# theMonarchTransmitter.net
KiCad netlist of a schematic drawn in Altium Designer
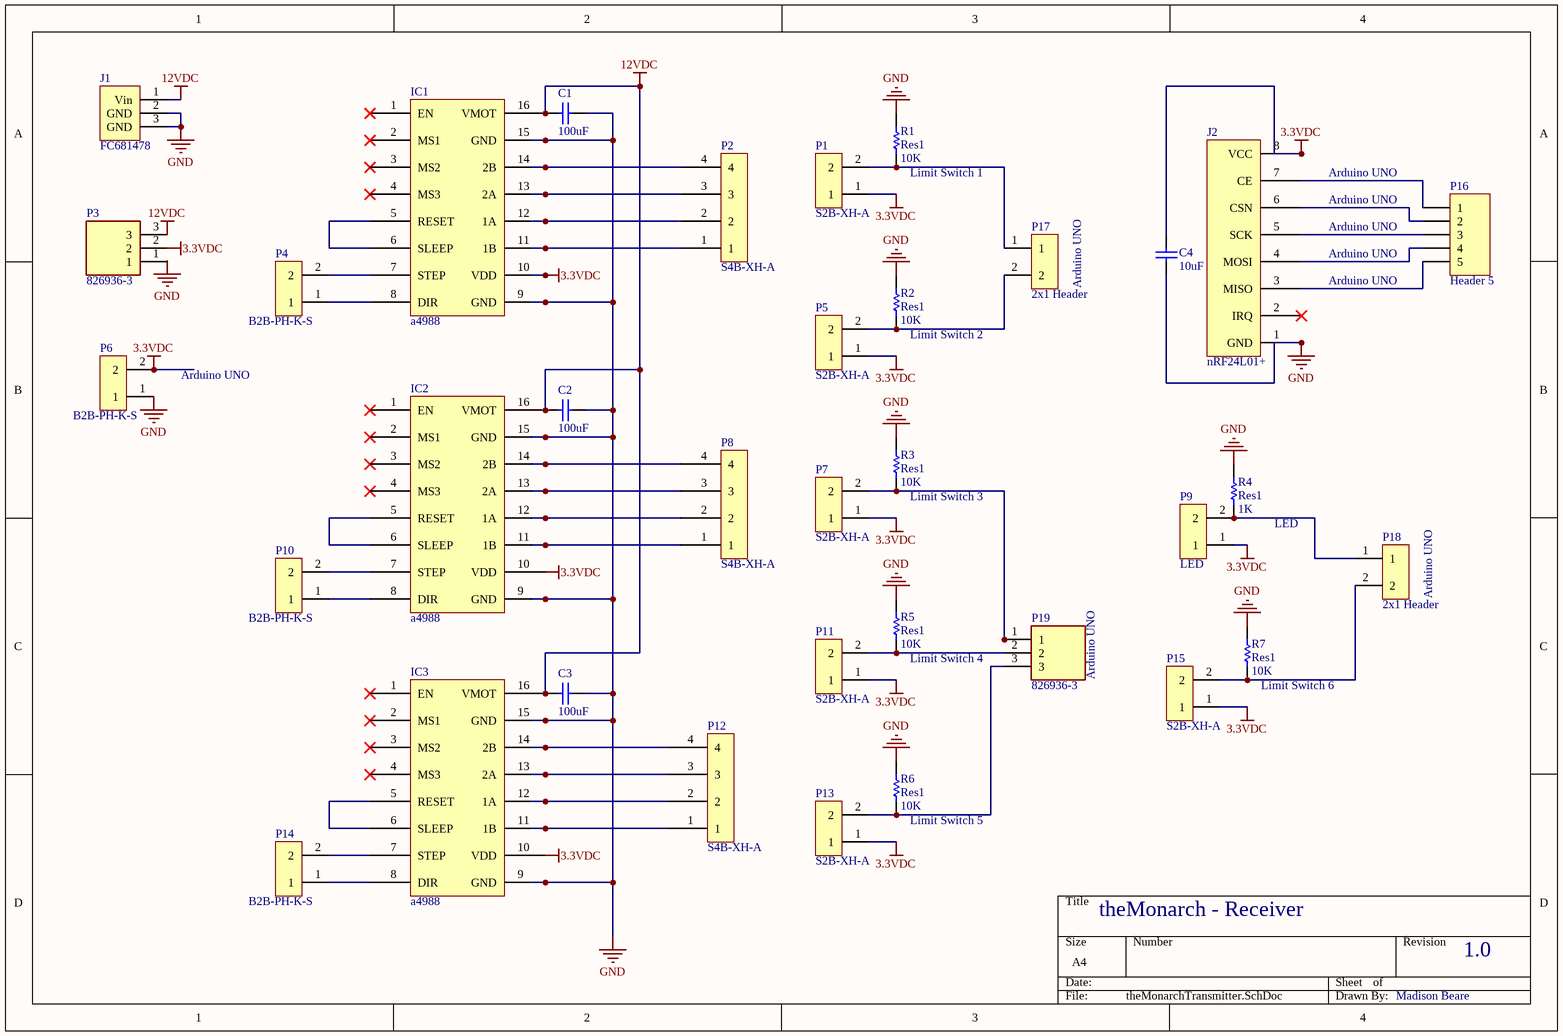
[diagram p0: theMonarchTransmitter.SchDoc]

(export (version "E")
  (design (tool "Eeschema 10.0.6"))
  (components
    (comp (ref "C1")
      (value "100uF")
      (footprint "RAD-0.3")
      (description "Capacitor")
      (fields (field (name "PUBLISHER") "Altium Limited"))
      (libsource (lib "Miscellaneous Devices") (part "Cap"))
    )
    (comp (ref "C2")
      (value "100uF")
      (footprint "RAD-0.3")
      (description "Capacitor")
      (fields (field (name "PUBLISHER") "Altium Limited"))
      (libsource (lib "Miscellaneous Devices") (part "Cap"))
    )
    (comp (ref "C3")
      (value "100uF")
      (footprint "RAD-0.3")
      (description "Capacitor")
      (fields (field (name "PUBLISHER") "Altium Limited"))
      (libsource (lib "Miscellaneous Devices") (part "Cap"))
    )
    (comp (ref "C4")
      (value "10uF")
      (footprint "RAD-0.3")
      (description "Capacitor")
      (fields (field (name "PUBLISHER") "Altium Limited"))
      (libsource (lib "Miscellaneous Devices") (part "Cap"))
    )
    (comp (ref "IC1")
      (value "a4988")
      (footprint "MODULE_A4988_STEPPER_MOTOR_DRIVER_CARRIER")
      (libsource (lib "theMonarchTransmitter_SchLib") (part "a4988"))
    )
    (comp (ref "IC2")
      (value "a4988")
      (footprint "MODULE_A4988_STEPPER_MOTOR_DRIVER_CARRIER")
      (libsource (lib "theMonarchTransmitter_SchLib") (part "a4988"))
    )
    (comp (ref "IC3")
      (value "a4988")
      (footprint "MODULE_A4988_STEPPER_MOTOR_DRIVER_CARRIER")
      (libsource (lib "theMonarchTransmitter_SchLib") (part "a4988"))
    )
    (comp (ref "J1")
      (value "FC681478")
      (footprint "FC681478")
      (description "CLIFF ELECTRONIC COMPONENTS         FC681478            CONNECTOR, POWER ENTRY, RCPT, 2A, 16VDC")
      (fields (field (name "MANUFACTURER") "Cliff"))
      (libsource (lib "theMonarchTransmitter_SchLib") (part "FC681478"))
    )
    (comp (ref "J2")
      (value "nRF24L01+")
      (footprint "TE_5-146278-8")
      (description "SPARKFUN TRANSCEIVER BREAKOUT -")
      (fields (field (name "MANUFACTURER") "SparkFun") (field (name "MANUFACTURER PART NUMBER") "WRL-00691"))
      (libsource (lib "theMonarchTransmitter_SchLib") (part "WRL-00691"))
    )
    (comp (ref "P1")
      (value "S2B-XH-A")
      (footprint "JST_S2B-XH-A(LF)(SN)")
      (description "Conn Shrouded Header HDR 2 POS 2.5mm Solder RA Thru-Hole Box")
      (fields
        (field (name "MANUFACTURER") "JST")
        (field (name "MANUFACTURER PART NUMBER") "S2B-XH-A(LF)(SN)")
      )
      (libsource (lib "theMonarchTransmitter_SchLib") (part "S2B-XH-A(LF)(SN)"))
    )
    (comp (ref "P2")
      (value "S4B-XH-A")
      (footprint "S4B-XH-A(LF)(SN)")
      (description "Conn Shrouded Header HDR 4 POS 2.5mm Solder RA Thru-Hole Box")
      (fields
        (field (name "MANUFACTURER") "JST")
        (field (name "MANUFACTURER PART NUMBER") "S4B-XH-A(LF)(SN)")
      )
      (libsource (lib "theMonarchTransmitter_SchLib") (part "S4B-XH-A(LF)(SN)"))
    )
    (comp (ref "P3")
      (value "826936-3")
      (footprint "TE_826936-3")
      (description "Connector Header Through Hole 3 position 0.100 (2.54mm)")
      (fields (field (name "MF") "TE Connectivity"))
      (libsource (lib "826936-3") (part "826936-3"))
    )
    (comp (ref "P4")
      (value "B2B-PH-K-S")
      (footprint "JST_B2B-PH-K-S(LF)(SN)")
      (description "Connector Header, PH Series, 2 Position, 2.00mm, Through Hole, Press-Fit, Solder, Natural")
      (fields
        (field (name "MANUFACTURER") "JST")
        (field (name "MANUFACTURER PART NUMBER") "B2B-PH-K-S(LF)(SN)")
      )
      (libsource (lib "theMonarchTransmitter_SchLib") (part "B2B-PH-K-S(LF)(SN)"))
    )
    (comp (ref "P5")
      (value "S2B-XH-A")
      (footprint "JST_S2B-XH-A(LF)(SN)")
      (description "Conn Shrouded Header HDR 2 POS 2.5mm Solder RA Thru-Hole Box")
      (fields
        (field (name "MANUFACTURER") "JST")
        (field (name "MANUFACTURER PART NUMBER") "S2B-XH-A(LF)(SN)")
      )
      (libsource (lib "theMonarchTransmitter_SchLib") (part "S2B-XH-A(LF)(SN)"))
    )
    (comp (ref "P6")
      (value "B2B-PH-K-S")
      (footprint "JST_B2B-PH-K-S(LF)(SN)")
      (description "Connector Header, PH Series, 2 Position, 2.00mm, Through Hole, Press-Fit, Solder, Natural")
      (fields
        (field (name "MANUFACTURER") "JST")
        (field (name "MANUFACTURER PART NUMBER") "B2B-PH-K-S(LF)(SN)")
      )
      (libsource (lib "theMonarchTransmitter_SchLib") (part "B2B-PH-K-S(LF)(SN)"))
    )
    (comp (ref "P7")
      (value "S2B-XH-A")
      (footprint "JST_S2B-XH-A(LF)(SN)")
      (description "Conn Shrouded Header HDR 2 POS 2.5mm Solder RA Thru-Hole Box")
      (fields
        (field (name "MANUFACTURER") "JST")
        (field (name "MANUFACTURER PART NUMBER") "S2B-XH-A(LF)(SN)")
      )
      (libsource (lib "theMonarchTransmitter_SchLib") (part "S2B-XH-A(LF)(SN)"))
    )
    (comp (ref "P8")
      (value "S4B-XH-A")
      (footprint "S4B-XH-A(LF)(SN)")
      (description "Conn Shrouded Header HDR 4 POS 2.5mm Solder RA Thru-Hole Box")
      (fields
        (field (name "MANUFACTURER") "JST")
        (field (name "MANUFACTURER PART NUMBER") "S4B-XH-A(LF)(SN)")
      )
      (libsource (lib "theMonarchTransmitter_SchLib") (part "S4B-XH-A(LF)(SN)"))
    )
    (comp (ref "P9")
      (value "LED")
      (footprint "HDR1X2")
      (description "Conn Shrouded Header HDR 2 POS 2.5mm Solder RA Thru-Hole Box")
      (fields
        (field (name "MANUFACTURER") "JST")
        (field (name "MANUFACTURER PART NUMBER") "S2B-XH-A(LF)(SN)")
      )
      (libsource (lib "theMonarchTransmitter_SchLib") (part "S2B-XH-A(LF)(SN)"))
    )
    (comp (ref "P10")
      (value "B2B-PH-K-S")
      (footprint "JST_B2B-PH-K-S(LF)(SN)")
      (description "Connector Header, PH Series, 2 Position, 2.00mm, Through Hole, Press-Fit, Solder, Natural")
      (fields
        (field (name "MANUFACTURER") "JST")
        (field (name "MANUFACTURER PART NUMBER") "B2B-PH-K-S(LF)(SN)")
      )
      (libsource (lib "theMonarchTransmitter_SchLib") (part "B2B-PH-K-S(LF)(SN)"))
    )
    (comp (ref "P11")
      (value "S2B-XH-A")
      (footprint "JST_S2B-XH-A(LF)(SN)")
      (description "Conn Shrouded Header HDR 2 POS 2.5mm Solder RA Thru-Hole Box")
      (fields
        (field (name "MANUFACTURER") "JST")
        (field (name "MANUFACTURER PART NUMBER") "S2B-XH-A(LF)(SN)")
      )
      (libsource (lib "theMonarchTransmitter_SchLib") (part "S2B-XH-A(LF)(SN)"))
    )
    (comp (ref "P12")
      (value "S4B-XH-A")
      (footprint "S4B-XH-A(LF)(SN)")
      (description "Conn Shrouded Header HDR 4 POS 2.5mm Solder RA Thru-Hole Box")
      (fields
        (field (name "MANUFACTURER") "JST")
        (field (name "MANUFACTURER PART NUMBER") "S4B-XH-A(LF)(SN)")
      )
      (libsource (lib "theMonarchTransmitter_SchLib") (part "S4B-XH-A(LF)(SN)"))
    )
    (comp (ref "P13")
      (value "S2B-XH-A")
      (footprint "JST_S2B-XH-A(LF)(SN)")
      (description "Conn Shrouded Header HDR 2 POS 2.5mm Solder RA Thru-Hole Box")
      (fields
        (field (name "MANUFACTURER") "JST")
        (field (name "MANUFACTURER PART NUMBER") "S2B-XH-A(LF)(SN)")
      )
      (libsource (lib "theMonarchTransmitter_SchLib") (part "S2B-XH-A(LF)(SN)"))
    )
    (comp (ref "P14")
      (value "B2B-PH-K-S")
      (footprint "JST_B2B-PH-K-S(LF)(SN)")
      (description "Connector Header, PH Series, 2 Position, 2.00mm, Through Hole, Press-Fit, Solder, Natural")
      (fields
        (field (name "MANUFACTURER") "JST")
        (field (name "MANUFACTURER PART NUMBER") "B2B-PH-K-S(LF)(SN)")
      )
      (libsource (lib "theMonarchTransmitter_SchLib") (part "B2B-PH-K-S(LF)(SN)"))
    )
    (comp (ref "P15")
      (value "S2B-XH-A")
      (footprint "JST_S2B-XH-A(LF)(SN)")
      (description "Conn Shrouded Header HDR 2 POS 2.5mm Solder RA Thru-Hole Box")
      (fields
        (field (name "MANUFACTURER") "JST")
        (field (name "MANUFACTURER PART NUMBER") "S2B-XH-A(LF)(SN)")
      )
      (libsource (lib "theMonarchTransmitter_SchLib") (part "S2B-XH-A(LF)(SN)"))
    )
    (comp (ref "P16")
      (value "Header 5")
      (footprint "HDR1X5")
      (description "Header, 5-Pin")
      (fields (field (name "PUBLISHER") "Altium Limited"))
      (libsource (lib "Miscellaneous Connectors") (part "Header 5"))
    )
    (comp (ref "P17")
      (value "2x1 Header")
      (footprint "JST_B2B-PH-K-S(LF)(SN)")
      (description "Conn Shrouded Header HDR 2 POS 2.5mm Solder RA Thru-Hole Box")
      (fields
        (field (name "MANUFACTURER") "JST")
        (field (name "MANUFACTURER PART NUMBER") "S2B-XH-A(LF)(SN)")
      )
      (libsource (lib "") (part "S2B-XH-A(LF)(SN)_1"))
    )
    (comp (ref "P18")
      (value "2x1 Header")
      (footprint "JST_B2B-PH-K-S(LF)(SN)")
      (description "Conn Shrouded Header HDR 2 POS 2.5mm Solder RA Thru-Hole Box")
      (fields
        (field (name "MANUFACTURER") "JST")
        (field (name "MANUFACTURER PART NUMBER") "S2B-XH-A(LF)(SN)")
      )
      (libsource (lib "") (part "S2B-XH-A(LF)(SN)_1"))
    )
    (comp (ref "P19")
      (value "826936-3")
      (footprint "TE_826936-3")
      (description "Connector Header Through Hole 3 position 0.100 (2.54mm)")
      (fields (field (name "MF") "TE Connectivity"))
      (libsource (lib "") (part "826936-3_1"))
    )
    (comp (ref "R1")
      (value "Res1")
      (footprint "AXIAL-0.3")
      (description "Resistor")
      (fields (field (name "ALTIUM_VALUE") "10K") (field (name "PUBLISHER") "Altium Limited"))
      (libsource (lib "Miscellaneous Devices") (part "Res1"))
    )
    (comp (ref "R2")
      (value "Res1")
      (footprint "AXIAL-0.3")
      (description "Resistor")
      (fields (field (name "ALTIUM_VALUE") "10K") (field (name "PUBLISHER") "Altium Limited"))
      (libsource (lib "Miscellaneous Devices") (part "Res1"))
    )
    (comp (ref "R3")
      (value "Res1")
      (footprint "AXIAL-0.3")
      (description "Resistor")
      (fields (field (name "ALTIUM_VALUE") "10K") (field (name "PUBLISHER") "Altium Limited"))
      (libsource (lib "Miscellaneous Devices") (part "Res1"))
    )
    (comp (ref "R4")
      (value "Res1")
      (footprint "AXIAL-0.3")
      (description "Resistor")
      (fields (field (name "ALTIUM_VALUE") "1K") (field (name "PUBLISHER") "Altium Limited"))
      (libsource (lib "Miscellaneous Devices") (part "Res1"))
    )
    (comp (ref "R5")
      (value "Res1")
      (footprint "AXIAL-0.3")
      (description "Resistor")
      (fields (field (name "ALTIUM_VALUE") "10K") (field (name "PUBLISHER") "Altium Limited"))
      (libsource (lib "Miscellaneous Devices") (part "Res1"))
    )
    (comp (ref "R6")
      (value "Res1")
      (footprint "AXIAL-0.3")
      (description "Resistor")
      (fields (field (name "ALTIUM_VALUE") "10K") (field (name "PUBLISHER") "Altium Limited"))
      (libsource (lib "Miscellaneous Devices") (part "Res1"))
    )
    (comp (ref "R7")
      (value "Res1")
      (footprint "AXIAL-0.3")
      (description "Resistor")
      (fields (field (name "ALTIUM_VALUE") "10K") (field (name "PUBLISHER") "Altium Limited"))
      (libsource (lib "Miscellaneous Devices") (part "Res1"))
    )
  )
  (nets
    (net (code "1") (name "3.3VDC") (class "Default")
      (node (ref "C4") (pin "2") (pinfunction "2_2") (pintype "passive"))
      (node (ref "IC1") (pin "10") (pinfunction "VDD_10") (pintype "passive"))
      (node (ref "IC2") (pin "10") (pinfunction "VDD_10") (pintype "passive"))
      (node (ref "IC3") (pin "10") (pinfunction "VDD_10") (pintype "passive"))
      (node (ref "J2") (pin "8") (pinfunction "VCC_8") (pintype "passive"))
      (node (ref "P1") (pin "1") (pinfunction "1_1") (pintype "passive"))
      (node (ref "P11") (pin "1") (pinfunction "1_1") (pintype "passive"))
      (node (ref "P13") (pin "1") (pinfunction "1_1") (pintype "passive"))
      (node (ref "P15") (pin "1") (pinfunction "1_1") (pintype "passive"))
      (node (ref "P3") (pin "2") (pinfunction "2_2") (pintype "passive"))
      (node (ref "P5") (pin "1") (pinfunction "1_1") (pintype "passive"))
      (node (ref "P6") (pin "2") (pinfunction "2_2") (pintype "passive"))
      (node (ref "P7") (pin "1") (pinfunction "1_1") (pintype "passive"))
      (node (ref "P9") (pin "1") (pinfunction "1_1") (pintype "passive"))
    )
    (net (code "2") (name "12VDC") (class "Default")
      (node (ref "C1") (pin "1") (pinfunction "1_1") (pintype "passive"))
      (node (ref "C2") (pin "1") (pinfunction "1_1") (pintype "passive"))
      (node (ref "C3") (pin "1") (pinfunction "1_1") (pintype "passive"))
      (node (ref "IC1") (pin "16") (pinfunction "VMOT_16") (pintype "passive"))
      (node (ref "IC2") (pin "16") (pinfunction "VMOT_16") (pintype "passive"))
      (node (ref "IC3") (pin "16") (pinfunction "VMOT_16") (pintype "passive"))
      (node (ref "J1") (pin "1") (pinfunction "Vin_1") (pintype "passive"))
      (node (ref "P3") (pin "3") (pinfunction "3_3") (pintype "passive"))
    )
    (net (code "3") (name "GND") (class "Default")
      (node (ref "C1") (pin "2") (pinfunction "2_2") (pintype "passive"))
      (node (ref "C2") (pin "2") (pinfunction "2_2") (pintype "passive"))
      (node (ref "C3") (pin "2") (pinfunction "2_2") (pintype "passive"))
      (node (ref "C4") (pin "1") (pinfunction "1_1") (pintype "passive"))
      (node (ref "IC1") (pin "15") (pinfunction "GND_15") (pintype "passive"))
      (node (ref "IC1") (pin "9") (pinfunction "GND_9") (pintype "passive"))
      (node (ref "IC2") (pin "15") (pinfunction "GND_15") (pintype "passive"))
      (node (ref "IC2") (pin "9") (pinfunction "GND_9") (pintype "passive"))
      (node (ref "IC3") (pin "15") (pinfunction "GND_15") (pintype "passive"))
      (node (ref "IC3") (pin "9") (pinfunction "GND_9") (pintype "passive"))
      (node (ref "J1") (pin "2") (pinfunction "GND_2") (pintype "passive"))
      (node (ref "J1") (pin "3") (pinfunction "GND_3") (pintype "passive"))
      (node (ref "J2") (pin "1") (pinfunction "GND_1") (pintype "passive"))
      (node (ref "P6") (pin "1") (pinfunction "1_1") (pintype "passive"))
      (node (ref "R1") (pin "2") (pinfunction "2_2") (pintype "passive"))
      (node (ref "R2") (pin "2") (pinfunction "2_2") (pintype "passive"))
      (node (ref "R3") (pin "2") (pinfunction "2_2") (pintype "passive"))
      (node (ref "R4") (pin "2") (pinfunction "2_2") (pintype "passive"))
      (node (ref "R5") (pin "2") (pinfunction "2_2") (pintype "passive"))
      (node (ref "R6") (pin "2") (pinfunction "2_2") (pintype "passive"))
      (node (ref "R7") (pin "2") (pinfunction "2_2") (pintype "passive"))
    )
    (net (code "4") (name "Net-(IC1-1A)") (class "Default")
      (node (ref "IC1") (pin "12") (pinfunction "1A_12") (pintype "passive"))
      (node (ref "P2") (pin "2") (pinfunction "2_2") (pintype "passive"))
    )
    (net (code "5") (name "Net-(IC1-1B)") (class "Default")
      (node (ref "IC1") (pin "11") (pinfunction "1B_11") (pintype "passive"))
      (node (ref "P2") (pin "1") (pinfunction "1_1") (pintype "passive"))
    )
    (net (code "6") (name "Net-(IC1-2A)") (class "Default")
      (node (ref "IC1") (pin "13") (pinfunction "2A_13") (pintype "passive"))
      (node (ref "P2") (pin "3") (pinfunction "3_3") (pintype "passive"))
    )
    (net (code "7") (name "Net-(IC1-2B)") (class "Default")
      (node (ref "IC1") (pin "14") (pinfunction "2B_14") (pintype "passive"))
      (node (ref "P2") (pin "4") (pinfunction "4_4") (pintype "passive"))
    )
    (net (code "8") (name "Net-(IC1-DIR)") (class "Default")
      (node (ref "IC1") (pin "8") (pinfunction "DIR_8") (pintype "passive"))
      (node (ref "P4") (pin "1") (pinfunction "1_1") (pintype "passive"))
    )
    (net (code "9") (name "Net-(IC1-RESET)") (class "Default")
      (node (ref "IC1") (pin "5") (pinfunction "RESET_5") (pintype "passive"))
      (node (ref "IC1") (pin "6") (pinfunction "SLEEP_6") (pintype "passive"))
    )
    (net (code "10") (name "Net-(IC1-STEP)") (class "Default")
      (node (ref "IC1") (pin "7") (pinfunction "STEP_7") (pintype "passive"))
      (node (ref "P4") (pin "2") (pinfunction "2_2") (pintype "passive"))
    )
    (net (code "11") (name "Net-(IC2-1A)") (class "Default")
      (node (ref "IC2") (pin "12") (pinfunction "1A_12") (pintype "passive"))
      (node (ref "P8") (pin "2") (pinfunction "2_2") (pintype "passive"))
    )
    (net (code "12") (name "Net-(IC2-1B)") (class "Default")
      (node (ref "IC2") (pin "11") (pinfunction "1B_11") (pintype "passive"))
      (node (ref "P8") (pin "1") (pinfunction "1_1") (pintype "passive"))
    )
    (net (code "13") (name "Net-(IC2-2A)") (class "Default")
      (node (ref "IC2") (pin "13") (pinfunction "2A_13") (pintype "passive"))
      (node (ref "P8") (pin "3") (pinfunction "3_3") (pintype "passive"))
    )
    (net (code "14") (name "Net-(IC2-2B)") (class "Default")
      (node (ref "IC2") (pin "14") (pinfunction "2B_14") (pintype "passive"))
      (node (ref "P8") (pin "4") (pinfunction "4_4") (pintype "passive"))
    )
    (net (code "15") (name "Net-(IC2-DIR)") (class "Default")
      (node (ref "IC2") (pin "8") (pinfunction "DIR_8") (pintype "passive"))
      (node (ref "P10") (pin "1") (pinfunction "1_1") (pintype "passive"))
    )
    (net (code "16") (name "Net-(IC2-RESET)") (class "Default")
      (node (ref "IC2") (pin "5") (pinfunction "RESET_5") (pintype "passive"))
      (node (ref "IC2") (pin "6") (pinfunction "SLEEP_6") (pintype "passive"))
    )
    (net (code "17") (name "Net-(IC2-STEP)") (class "Default")
      (node (ref "IC2") (pin "7") (pinfunction "STEP_7") (pintype "passive"))
      (node (ref "P10") (pin "2") (pinfunction "2_2") (pintype "passive"))
    )
    (net (code "18") (name "Net-(IC3-1A)") (class "Default")
      (node (ref "IC3") (pin "12") (pinfunction "1A_12") (pintype "passive"))
      (node (ref "P12") (pin "2") (pinfunction "2_2") (pintype "passive"))
    )
    (net (code "19") (name "Net-(IC3-1B)") (class "Default")
      (node (ref "IC3") (pin "11") (pinfunction "1B_11") (pintype "passive"))
      (node (ref "P12") (pin "1") (pinfunction "1_1") (pintype "passive"))
    )
    (net (code "20") (name "Net-(IC3-2A)") (class "Default")
      (node (ref "IC3") (pin "13") (pinfunction "2A_13") (pintype "passive"))
      (node (ref "P12") (pin "3") (pinfunction "3_3") (pintype "passive"))
    )
    (net (code "21") (name "Net-(IC3-2B)") (class "Default")
      (node (ref "IC3") (pin "14") (pinfunction "2B_14") (pintype "passive"))
      (node (ref "P12") (pin "4") (pinfunction "4_4") (pintype "passive"))
    )
    (net (code "22") (name "Net-(IC3-DIR)") (class "Default")
      (node (ref "IC3") (pin "8") (pinfunction "DIR_8") (pintype "passive"))
      (node (ref "P14") (pin "1") (pinfunction "1_1") (pintype "passive"))
    )
    (net (code "23") (name "Net-(IC3-RESET)") (class "Default")
      (node (ref "IC3") (pin "5") (pinfunction "RESET_5") (pintype "passive"))
      (node (ref "IC3") (pin "6") (pinfunction "SLEEP_6") (pintype "passive"))
    )
    (net (code "24") (name "Net-(IC3-STEP)") (class "Default")
      (node (ref "IC3") (pin "7") (pinfunction "STEP_7") (pintype "passive"))
      (node (ref "P14") (pin "2") (pinfunction "2_2") (pintype "passive"))
    )
    (net (code "25") (name "Net-(J2-CE)") (class "Default")
      (node (ref "J2") (pin "7") (pinfunction "CE_7") (pintype "passive"))
      (node (ref "P16") (pin "1") (pinfunction "1_1") (pintype "passive"))
    )
    (net (code "26") (name "Net-(J2-CSN)") (class "Default")
      (node (ref "J2") (pin "6") (pinfunction "CSN_6") (pintype "passive"))
      (node (ref "P16") (pin "2") (pinfunction "2_2") (pintype "passive"))
    )
    (net (code "27") (name "Net-(J2-MISO)") (class "Default")
      (node (ref "J2") (pin "3") (pinfunction "MISO_3") (pintype "passive"))
      (node (ref "P16") (pin "5") (pinfunction "5_5") (pintype "passive"))
    )
    (net (code "28") (name "Net-(J2-MOSI)") (class "Default")
      (node (ref "J2") (pin "4") (pinfunction "MOSI_4") (pintype "passive"))
      (node (ref "P16") (pin "4") (pinfunction "4_4") (pintype "passive"))
    )
    (net (code "29") (name "Net-(J2-SCK)") (class "Default")
      (node (ref "J2") (pin "5") (pinfunction "SCK_5") (pintype "passive"))
      (node (ref "P16") (pin "3") (pinfunction "3_3") (pintype "passive"))
    )
    (net (code "30") (name "Net-(P1-Pad2)") (class "Default")
      (node (ref "P1") (pin "2") (pinfunction "2_2") (pintype "passive"))
      (node (ref "P17") (pin "1") (pinfunction "1_1") (pintype "passive"))
      (node (ref "R1") (pin "1") (pinfunction "1_1") (pintype "passive"))
    )
    (net (code "31") (name "Net-(P11-Pad2)") (class "Default")
      (node (ref "P11") (pin "2") (pinfunction "2_2") (pintype "passive"))
      (node (ref "P19") (pin "2") (pinfunction "2_2") (pintype "passive"))
      (node (ref "R5") (pin "1") (pinfunction "1_1") (pintype "passive"))
    )
    (net (code "32") (name "Net-(P13-Pad2)") (class "Default")
      (node (ref "P13") (pin "2") (pinfunction "2_2") (pintype "passive"))
      (node (ref "P19") (pin "3") (pinfunction "3_3") (pintype "passive"))
      (node (ref "R6") (pin "1") (pinfunction "1_1") (pintype "passive"))
    )
    (net (code "33") (name "Net-(P15-Pad2)") (class "Default")
      (node (ref "P15") (pin "2") (pinfunction "2_2") (pintype "passive"))
      (node (ref "P18") (pin "2") (pinfunction "2_2") (pintype "passive"))
      (node (ref "R7") (pin "1") (pinfunction "1_1") (pintype "passive"))
    )
    (net (code "34") (name "Net-(P17-Pad2)") (class "Default")
      (node (ref "P17") (pin "2") (pinfunction "2_2") (pintype "passive"))
      (node (ref "P5") (pin "2") (pinfunction "2_2") (pintype "passive"))
      (node (ref "R2") (pin "1") (pinfunction "1_1") (pintype "passive"))
    )
    (net (code "35") (name "Net-(P18-Pad1)") (class "Default")
      (node (ref "P18") (pin "1") (pinfunction "1_1") (pintype "passive"))
      (node (ref "P9") (pin "2") (pinfunction "2_2") (pintype "passive"))
      (node (ref "R4") (pin "1") (pinfunction "1_1") (pintype "passive"))
    )
    (net (code "36") (name "Net-(P19-Pad1)") (class "Default")
      (node (ref "P19") (pin "1") (pinfunction "1_1") (pintype "passive"))
      (node (ref "P7") (pin "2") (pinfunction "2_2") (pintype "passive"))
      (node (ref "R3") (pin "1") (pinfunction "1_1") (pintype "passive"))
    )
    (net (code "37") (name "unconnected-(IC1-EN-Pad1)") (class "Default")
      (node (ref "IC1") (pin "1") (pinfunction "EN_1") (pintype "passive+no_connect"))
    )
    (net (code "38") (name "unconnected-(IC1-MS1-Pad2)") (class "Default")
      (node (ref "IC1") (pin "2") (pinfunction "MS1_2") (pintype "passive+no_connect"))
    )
    (net (code "39") (name "unconnected-(IC1-MS2-Pad3)") (class "Default")
      (node (ref "IC1") (pin "3") (pinfunction "MS2_3") (pintype "passive+no_connect"))
    )
    (net (code "40") (name "unconnected-(IC1-MS3-Pad4)") (class "Default")
      (node (ref "IC1") (pin "4") (pinfunction "MS3_4") (pintype "passive+no_connect"))
    )
    (net (code "41") (name "unconnected-(IC2-EN-Pad1)") (class "Default")
      (node (ref "IC2") (pin "1") (pinfunction "EN_1") (pintype "passive+no_connect"))
    )
    (net (code "42") (name "unconnected-(IC2-MS1-Pad2)") (class "Default")
      (node (ref "IC2") (pin "2") (pinfunction "MS1_2") (pintype "passive+no_connect"))
    )
    (net (code "43") (name "unconnected-(IC2-MS2-Pad3)") (class "Default")
      (node (ref "IC2") (pin "3") (pinfunction "MS2_3") (pintype "passive+no_connect"))
    )
    (net (code "44") (name "unconnected-(IC2-MS3-Pad4)") (class "Default")
      (node (ref "IC2") (pin "4") (pinfunction "MS3_4") (pintype "passive+no_connect"))
    )
    (net (code "45") (name "unconnected-(IC3-EN-Pad1)") (class "Default")
      (node (ref "IC3") (pin "1") (pinfunction "EN_1") (pintype "passive+no_connect"))
    )
    (net (code "46") (name "unconnected-(IC3-MS1-Pad2)") (class "Default")
      (node (ref "IC3") (pin "2") (pinfunction "MS1_2") (pintype "passive+no_connect"))
    )
    (net (code "47") (name "unconnected-(IC3-MS2-Pad3)") (class "Default")
      (node (ref "IC3") (pin "3") (pinfunction "MS2_3") (pintype "passive+no_connect"))
    )
    (net (code "48") (name "unconnected-(IC3-MS3-Pad4)") (class "Default")
      (node (ref "IC3") (pin "4") (pinfunction "MS3_4") (pintype "passive+no_connect"))
    )
    (net (code "49") (name "unconnected-(J2-IRQ-Pad2)") (class "Default")
      (node (ref "J2") (pin "2") (pinfunction "IRQ_2") (pintype "passive+no_connect"))
    )
    (net (code "50") (name "unconnected-(P3-Pad1)") (class "Default")
      (node (ref "P3") (pin "1") (pinfunction "1_1") (pintype "passive"))
    )
  )
)
